# BoardNeu.net
KiCad netlist of a schematic drawn in EAGLE
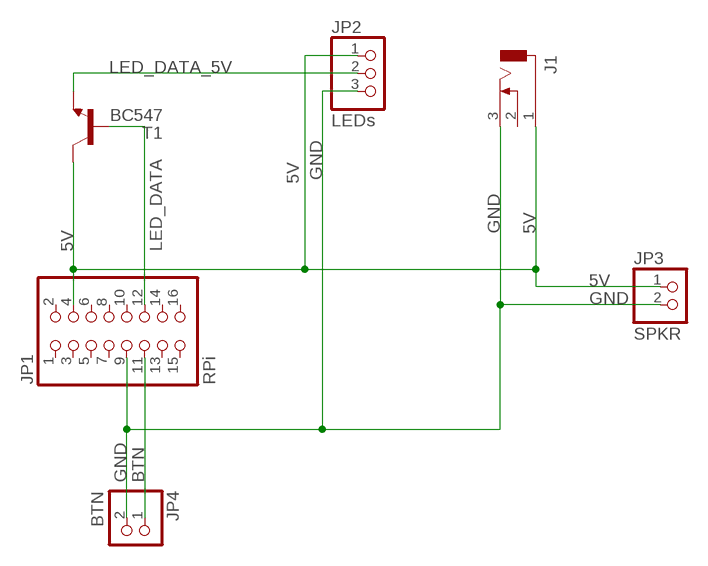
[diagram p0: schematic, sheet 1]

(export (version "E")
  (design (tool "Eeschema 10.0.6"))
  (components
    (comp (ref "J1")
      (value "DCJ0303")
      (footprint "eagle-import:DCJ0303")
      (libsource (lib "eagle-import") (part "DCJ0303"))
    )
    (comp (ref "JP1")
      (value "RPi")
      (footprint "eagle-import:2X08")
      (libsource (lib "eagle-import") (part "PINHD-2X8"))
    )
    (comp (ref "JP2")
      (value "LEDs")
      (footprint "eagle-import:1X03")
      (libsource (lib "eagle-import") (part "PINHD-1X3"))
    )
    (comp (ref "JP3")
      (value "SPKR")
      (footprint "eagle-import:1X02")
      (libsource (lib "eagle-import") (part "PINHD-1X2"))
    )
    (comp (ref "JP4")
      (value "BTN")
      (footprint "eagle-import:1X02")
      (libsource (lib "eagle-import") (part "PINHD-1X2"))
    )
    (comp (ref "T1")
      (value "BC547")
      (footprint "eagle-import:TO92")
      (libsource (lib "eagle-import") (part "BC547"))
    )
  )
  (nets
    (net (code "1") (name "/5V") (class "Default")
      (node (ref "J1") (pin "1") (pinfunction "1_1") (pintype "passive"))
      (node (ref "JP1") (pin "4") (pinfunction "4_4") (pintype "passive"))
      (node (ref "JP2") (pin "1") (pinfunction "1_1") (pintype "passive"))
      (node (ref "JP3") (pin "1") (pinfunction "1_1") (pintype "passive"))
      (node (ref "T1") (pin "3") (pinfunction "C_3") (pintype "passive"))
    )
    (net (code "2") (name "/BTN") (class "Default")
      (node (ref "JP1") (pin "11") (pinfunction "11_11") (pintype "passive"))
      (node (ref "JP4") (pin "1") (pinfunction "1_1") (pintype "passive"))
    )
    (net (code "3") (name "/GND") (class "Default")
      (node (ref "J1") (pin "3") (pinfunction "3_3") (pintype "passive"))
      (node (ref "JP1") (pin "9") (pinfunction "9_9") (pintype "passive"))
      (node (ref "JP2") (pin "3") (pinfunction "3_3") (pintype "passive"))
      (node (ref "JP3") (pin "2") (pinfunction "2_2") (pintype "passive"))
      (node (ref "JP4") (pin "2") (pinfunction "2_2") (pintype "passive"))
    )
    (net (code "4") (name "/LED_DATA") (class "Default")
      (node (ref "JP1") (pin "12") (pinfunction "12_12") (pintype "passive"))
      (node (ref "T1") (pin "2") (pinfunction "B_2") (pintype "passive"))
    )
    (net (code "5") (name "/LED_DATA_5V") (class "Default")
      (node (ref "JP2") (pin "2") (pinfunction "2_2") (pintype "passive"))
      (node (ref "T1") (pin "1") (pinfunction "E_1") (pintype "passive"))
    )
    (net (code "6") (name "unconnected-(J1-Pad2)") (class "Default")
      (node (ref "J1") (pin "2") (pinfunction "2_2") (pintype "passive"))
    )
    (net (code "7") (name "unconnected-(JP1-Pad1)") (class "Default")
      (node (ref "JP1") (pin "1") (pinfunction "1_1") (pintype "passive"))
    )
    (net (code "8") (name "unconnected-(JP1-Pad2)") (class "Default")
      (node (ref "JP1") (pin "2") (pinfunction "2_2") (pintype "passive"))
    )
    (net (code "9") (name "unconnected-(JP1-Pad3)") (class "Default")
      (node (ref "JP1") (pin "3") (pinfunction "3_3") (pintype "passive"))
    )
    (net (code "10") (name "unconnected-(JP1-Pad5)") (class "Default")
      (node (ref "JP1") (pin "5") (pinfunction "5_5") (pintype "passive"))
    )
    (net (code "11") (name "unconnected-(JP1-Pad6)") (class "Default")
      (node (ref "JP1") (pin "6") (pinfunction "6_6") (pintype "passive"))
    )
    (net (code "12") (name "unconnected-(JP1-Pad7)") (class "Default")
      (node (ref "JP1") (pin "7") (pinfunction "7_7") (pintype "passive"))
    )
    (net (code "13") (name "unconnected-(JP1-Pad8)") (class "Default")
      (node (ref "JP1") (pin "8") (pinfunction "8_8") (pintype "passive"))
    )
    (net (code "14") (name "unconnected-(JP1-Pad10)") (class "Default")
      (node (ref "JP1") (pin "10") (pinfunction "10_10") (pintype "passive"))
    )
    (net (code "15") (name "unconnected-(JP1-Pad13)") (class "Default")
      (node (ref "JP1") (pin "13") (pinfunction "13_13") (pintype "passive"))
    )
    (net (code "16") (name "unconnected-(JP1-Pad14)") (class "Default")
      (node (ref "JP1") (pin "14") (pinfunction "14_14") (pintype "passive"))
    )
    (net (code "17") (name "unconnected-(JP1-Pad15)") (class "Default")
      (node (ref "JP1") (pin "15") (pinfunction "15_15") (pintype "passive"))
    )
    (net (code "18") (name "unconnected-(JP1-Pad16)") (class "Default")
      (node (ref "JP1") (pin "16") (pinfunction "16_16") (pintype "passive"))
    )
  )
)
